# Controller.net
KiCad netlist of a schematic drawn in Altium Designer
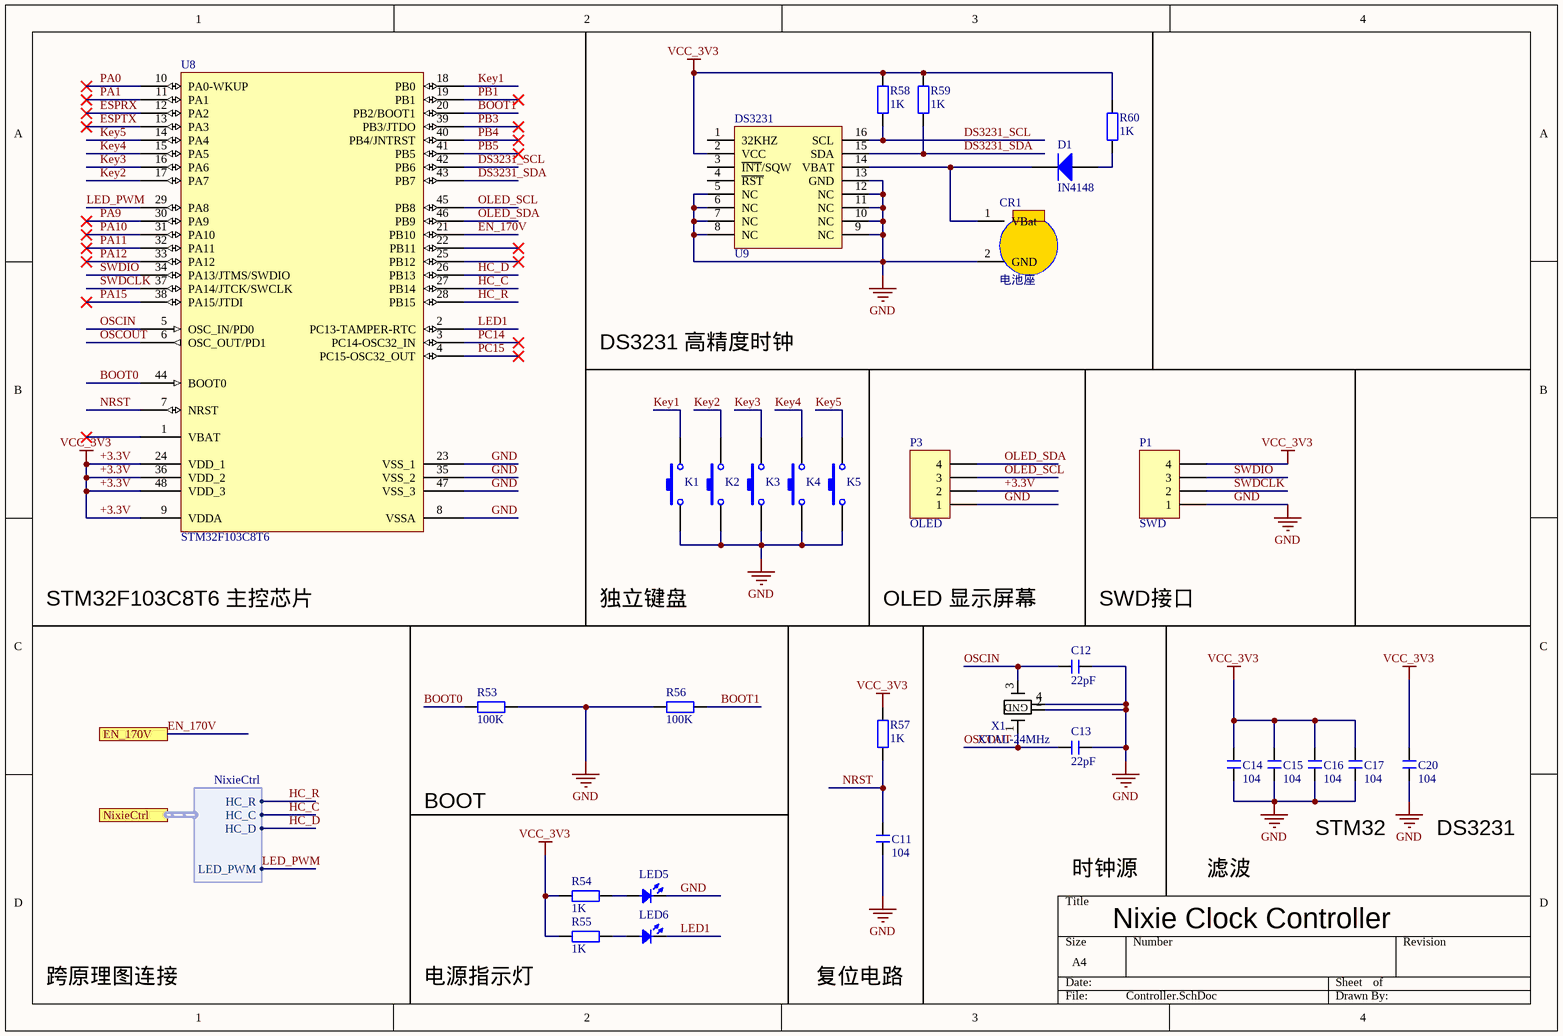
[diagram p0: Controller.SchDoc]

(export (version "E")
  (design (tool "Eeschema 10.0.6"))
  (components
    (comp (ref "C11")
      (value "104")
      (footprint "C 0603")
      (description "无极性贴片电容")
      (fields (field (name "版权归属") "源创客"))
      (libsource (lib "电阻-电容-电感") (part "C"))
    )
    (comp (ref "C12")
      (value "22pF")
      (footprint "C 0603")
      (description "无极性贴片电容")
      (fields (field (name "版权归属") "源创客"))
      (libsource (lib "电阻-电容-电感") (part "C"))
    )
    (comp (ref "C13")
      (value "22pF")
      (footprint "C 0603")
      (description "无极性贴片电容")
      (fields (field (name "版权归属") "源创客"))
      (libsource (lib "电阻-电容-电感") (part "C"))
    )
    (comp (ref "C14")
      (value "104")
      (footprint "C 0603")
      (description "无极性贴片电容")
      (fields (field (name "版权归属") "源创客"))
      (libsource (lib "电阻-电容-电感") (part "C"))
    )
    (comp (ref "C15")
      (value "104")
      (footprint "C 0603")
      (description "无极性贴片电容")
      (fields (field (name "版权归属") "源创客"))
      (libsource (lib "电阻-电容-电感") (part "C"))
    )
    (comp (ref "C16")
      (value "104")
      (footprint "C 0603")
      (description "无极性贴片电容")
      (fields (field (name "版权归属") "源创客"))
      (libsource (lib "电阻-电容-电感") (part "C"))
    )
    (comp (ref "C17")
      (value "104")
      (footprint "C 0603")
      (description "无极性贴片电容")
      (fields (field (name "版权归属") "源创客"))
      (libsource (lib "电阻-电容-电感") (part "C"))
    )
    (comp (ref "C20")
      (value "104")
      (footprint "C 0603")
      (description "无极性贴片电容")
      (fields (field (name "版权归属") "源创客"))
      (libsource (lib "电阻-电容-电感") (part "C"))
    )
    (comp (ref "CR1") (value "电池座") (footprint "BAT-2P") (libsource (lib "常用元件库") (part "CR2032 电池座")))
    (comp (ref "D1") (value "IN4148") (footprint "0805D") (libsource (lib "常用元件库") (part "二级管")))
    (comp (ref "K1") (value "按键") (footprint "TSW 3*6*4.3-S-W") (libsource (lib "常用元件库") (part "按键")))
    (comp (ref "K2") (value "按键") (footprint "TSW 3*6*4.3-S-W") (libsource (lib "常用元件库") (part "按键")))
    (comp (ref "K3") (value "按键") (footprint "TSW 3*6*4.3-S-W") (libsource (lib "常用元件库") (part "按键")))
    (comp (ref "K4") (value "按键") (footprint "TSW 3*6*4.3-S-W") (libsource (lib "常用元件库") (part "按键")))
    (comp (ref "K5") (value "按键") (footprint "TSW 3*6*4.3-S-W") (libsource (lib "常用元件库") (part "按键")))
    (comp (ref "LED5")
      (value "LED")
      (footprint "0805D")
      (fields (field (name "PUBLISHER") "Altium Limited"))
      (libsource (lib "常用元件库") (part "LED"))
    )
    (comp (ref "LED6")
      (value "LED")
      (footprint "0805D")
      (fields (field (name "PUBLISHER") "Altium Limited"))
      (libsource (lib "常用元件库") (part "LED"))
    )
    (comp (ref "P1")
      (value "SWD")
      (footprint "HDR1X4")
      (description "Header, 4-Pin")
      (fields (field (name "PUBLISHER") "Altium Limited"))
      (libsource (lib "Miscellaneous Connectors") (part "Header 4"))
    )
    (comp (ref "P3")
      (value "OLED")
      (footprint "HDR1X4")
      (description "Header, 4-Pin")
      (fields (field (name "PUBLISHER") "Altium Limited"))
      (libsource (lib "Miscellaneous Connectors") (part "Header 4"))
    )
    (comp (ref "R53")
      (value "100K")
      (footprint "R 0603")
      (description "贴片电阻")
      (fields (field (name "版权归属") "源创客"))
      (libsource (lib "电阻-电容-电感") (part "R"))
    )
    (comp (ref "R54")
      (value "1K")
      (footprint "R 0603")
      (description "贴片电阻")
      (fields (field (name "版权归属") "源创客"))
      (libsource (lib "电阻-电容-电感") (part "R"))
    )
    (comp (ref "R55")
      (value "1K")
      (footprint "R 0603")
      (description "贴片电阻")
      (fields (field (name "版权归属") "源创客"))
      (libsource (lib "电阻-电容-电感") (part "R"))
    )
    (comp (ref "R56")
      (value "100K")
      (footprint "R 0603")
      (description "贴片电阻")
      (fields (field (name "版权归属") "源创客"))
      (libsource (lib "电阻-电容-电感") (part "R"))
    )
    (comp (ref "R57")
      (value "1K")
      (footprint "R 0603")
      (description "贴片电阻")
      (fields (field (name "版权归属") "源创客"))
      (libsource (lib "电阻-电容-电感") (part "R"))
    )
    (comp (ref "R58")
      (value "1K")
      (footprint "R 0603")
      (description "贴片电阻")
      (fields (field (name "版权归属") "源创客"))
      (libsource (lib "电阻-电容-电感") (part "R"))
    )
    (comp (ref "R59")
      (value "1K")
      (footprint "R 0603")
      (description "贴片电阻")
      (fields (field (name "版权归属") "源创客"))
      (libsource (lib "电阻-电容-电感") (part "R"))
    )
    (comp (ref "R60")
      (value "1K")
      (footprint "R 0603")
      (description "贴片电阻")
      (fields (field (name "版权归属") "源创客"))
      (libsource (lib "电阻-电容-电感") (part "R"))
    )
    (comp (ref "U8")
      (value "STM32F103C8T6")
      (footprint "LQFP48 7X7_M")
      (description "Flaah:64/RAM:20/IO:36")
      (fields (field (name "版权归属") "源创客"))
      (libsource (lib "STM32系列单片机") (part "STM32F103C8T6"))
    )
    (comp (ref "U9") (value "DS3231") (footprint "SOL-16") (libsource (lib "常用元件库") (part "DS3231")))
    (comp (ref "X1")
      (value "XTAL-24MHz")
      (footprint "XTAL-3225")
      (libsource (lib "7426SCH") (part "XTAL-SMD"))
    )
  )
  (nets
    (net (code "2") (name "/BOOT0") (class "Default")
      (node (ref "R53") (pin "1") (pinfunction "1_1") (pintype "passive"))
      (node (ref "U8") (pin "44") (pinfunction "BOOT0_44") (pintype "input"))
    )
    (net (code "3") (name "/BOOT1") (class "Default")
      (node (ref "R56") (pin "2") (pinfunction "2_2") (pintype "passive"))
      (node (ref "U8") (pin "20") (pinfunction "PB2/BOOT1_20") (pintype "bidirectional"))
    )
    (net (code "4") (name "/DS3231_SCL") (class "Default")
      (node (ref "R58") (pin "1") (pinfunction "1_1") (pintype "passive"))
      (node (ref "U8") (pin "42") (pinfunction "PB6_42") (pintype "bidirectional"))
      (node (ref "U9") (pin "16") (pinfunction "SCL_16") (pintype "passive"))
    )
    (net (code "5") (name "/DS3231_SDA") (class "Default")
      (node (ref "R59") (pin "1") (pinfunction "1_1") (pintype "passive"))
      (node (ref "U8") (pin "43") (pinfunction "PB7_43") (pintype "bidirectional"))
      (node (ref "U9") (pin "15") (pinfunction "SDA_15") (pintype "passive"))
    )
    (net (code "6") (name "/EN_170V") (class "Default")
      (node (ref "U8") (pin "21") (pinfunction "PB10_21") (pintype "bidirectional"))
    )
    (net (code "7") (name "/ESPRX") (class "Default")
      (node (ref "U8") (pin "12") (pinfunction "PA2_12") (pintype "bidirectional+no_connect"))
    )
    (net (code "8") (name "/ESPTX") (class "Default")
      (node (ref "U8") (pin "13") (pinfunction "PA3_13") (pintype "bidirectional+no_connect"))
    )
    (net (code "9") (name "/HC_C") (class "Default")
      (node (ref "U8") (pin "27") (pinfunction "PB14_27") (pintype "bidirectional"))
    )
    (net (code "10") (name "/HC_D") (class "Default")
      (node (ref "U8") (pin "26") (pinfunction "PB13_26") (pintype "bidirectional"))
    )
    (net (code "11") (name "/HC_R") (class "Default")
      (node (ref "U8") (pin "28") (pinfunction "PB15_28") (pintype "bidirectional"))
    )
    (net (code "12") (name "/Key1") (class "Default")
      (node (ref "K1") (pin "2") (pinfunction "2_2") (pintype "passive"))
      (node (ref "U8") (pin "18") (pinfunction "PB0_18") (pintype "bidirectional"))
    )
    (net (code "13") (name "/Key2") (class "Default")
      (node (ref "K2") (pin "2") (pinfunction "2_2") (pintype "passive"))
      (node (ref "U8") (pin "17") (pinfunction "PA7_17") (pintype "bidirectional"))
    )
    (net (code "14") (name "/Key3") (class "Default")
      (node (ref "K3") (pin "2") (pinfunction "2_2") (pintype "passive"))
      (node (ref "U8") (pin "16") (pinfunction "PA6_16") (pintype "bidirectional"))
    )
    (net (code "15") (name "/Key4") (class "Default")
      (node (ref "K4") (pin "2") (pinfunction "2_2") (pintype "passive"))
      (node (ref "U8") (pin "15") (pinfunction "PA5_15") (pintype "bidirectional"))
    )
    (net (code "16") (name "/Key5") (class "Default")
      (node (ref "K5") (pin "2") (pinfunction "2_2") (pintype "passive"))
      (node (ref "U8") (pin "14") (pinfunction "PA4_14") (pintype "bidirectional"))
    )
    (net (code "17") (name "/LED1") (class "Default")
      (node (ref "LED6") (pin "2") (pinfunction "K_2") (pintype "passive"))
      (node (ref "U8") (pin "2") (pinfunction "PC13-TAMPER-RTC_2") (pintype "bidirectional"))
    )
    (net (code "18") (name "/LED_PWM") (class "Default")
      (node (ref "U8") (pin "29") (pinfunction "PA8_29") (pintype "bidirectional"))
    )
    (net (code "19") (name "/NRST") (class "Default")
      (node (ref "C11") (pin "2") (pinfunction "2_2") (pintype "passive"))
      (node (ref "R57") (pin "1") (pinfunction "1_1") (pintype "passive"))
      (node (ref "U8") (pin "7") (pinfunction "NRST_7") (pintype "bidirectional"))
    )
    (net (code "20") (name "/OLED_SCL") (class "Default")
      (node (ref "P3") (pin "3") (pinfunction "3_3") (pintype "passive"))
      (node (ref "U8") (pin "45") (pinfunction "PB8_45") (pintype "bidirectional"))
    )
    (net (code "21") (name "/OLED_SDA") (class "Default")
      (node (ref "P3") (pin "4") (pinfunction "4_4") (pintype "passive"))
      (node (ref "U8") (pin "46") (pinfunction "PB9_46") (pintype "bidirectional"))
    )
    (net (code "22") (name "/OSCIN") (class "Default")
      (node (ref "C12") (pin "1") (pinfunction "1_1") (pintype "passive"))
      (node (ref "U8") (pin "5") (pinfunction "OSC_IN/PD0_5") (pintype "input"))
      (node (ref "X1") (pin "3") (pinfunction "GND_3") (pintype "power_in"))
    )
    (net (code "23") (name "/OSCOUT") (class "Default")
      (node (ref "C13") (pin "1") (pinfunction "1_1") (pintype "passive"))
      (node (ref "U8") (pin "6") (pinfunction "OSC_OUT/PD1_6") (pintype "output"))
      (node (ref "X1") (pin "1") (pintype "bidirectional"))
    )
    (net (code "24") (name "/PA0") (class "Default")
      (node (ref "U8") (pin "10") (pinfunction "PA0-WKUP_10") (pintype "bidirectional+no_connect"))
    )
    (net (code "25") (name "/PA1") (class "Default")
      (node (ref "U8") (pin "11") (pinfunction "PA1_11") (pintype "bidirectional+no_connect"))
    )
    (net (code "26") (name "/PA9") (class "Default")
      (node (ref "U8") (pin "30") (pinfunction "PA9_30") (pintype "bidirectional+no_connect"))
    )
    (net (code "27") (name "/PA10") (class "Default")
      (node (ref "U8") (pin "31") (pinfunction "PA10_31") (pintype "bidirectional+no_connect"))
    )
    (net (code "28") (name "/PA11") (class "Default")
      (node (ref "U8") (pin "32") (pinfunction "PA11_32") (pintype "bidirectional+no_connect"))
    )
    (net (code "29") (name "/PA12") (class "Default")
      (node (ref "U8") (pin "33") (pinfunction "PA12_33") (pintype "bidirectional+no_connect"))
    )
    (net (code "30") (name "/PA15") (class "Default")
      (node (ref "U8") (pin "38") (pinfunction "PA15/JTDI_38") (pintype "bidirectional+no_connect"))
    )
    (net (code "31") (name "/PB1") (class "Default")
      (node (ref "U8") (pin "19") (pinfunction "PB1_19") (pintype "bidirectional+no_connect"))
    )
    (net (code "32") (name "/PB3") (class "Default")
      (node (ref "U8") (pin "39") (pinfunction "PB3/JTDO_39") (pintype "bidirectional+no_connect"))
    )
    (net (code "33") (name "/PB4") (class "Default")
      (node (ref "U8") (pin "40") (pinfunction "PB4/JNTRST_40") (pintype "bidirectional+no_connect"))
    )
    (net (code "34") (name "/PB5") (class "Default")
      (node (ref "U8") (pin "41") (pinfunction "PB5_41") (pintype "bidirectional+no_connect"))
    )
    (net (code "35") (name "/PC14") (class "Default")
      (node (ref "U8") (pin "3") (pinfunction "PC14-OSC32_IN_3") (pintype "bidirectional+no_connect"))
    )
    (net (code "36") (name "/PC15") (class "Default")
      (node (ref "U8") (pin "4") (pinfunction "PC15-OSC32_OUT_4") (pintype "bidirectional+no_connect"))
    )
    (net (code "37") (name "/SWDCLK") (class "Default")
      (node (ref "P1") (pin "2") (pinfunction "2_2") (pintype "passive"))
      (node (ref "U8") (pin "37") (pinfunction "PA14/JTCK/SWCLK_37") (pintype "bidirectional"))
    )
    (net (code "38") (name "/SWDIO") (class "Default")
      (node (ref "P1") (pin "3") (pinfunction "3_3") (pintype "passive"))
      (node (ref "U8") (pin "34") (pinfunction "PA13/JTMS/SWDIO_34") (pintype "bidirectional"))
    )
    (net (code "40") (name "GND") (class "Default")
      (node (ref "C11") (pin "1") (pinfunction "1_1") (pintype "passive"))
      (node (ref "C12") (pin "2") (pinfunction "2_2") (pintype "passive"))
      (node (ref "C13") (pin "2") (pinfunction "2_2") (pintype "passive"))
      (node (ref "C14") (pin "2") (pinfunction "2_2") (pintype "passive"))
      (node (ref "C15") (pin "2") (pinfunction "2_2") (pintype "passive"))
      (node (ref "C16") (pin "2") (pinfunction "2_2") (pintype "passive"))
      (node (ref "C17") (pin "2") (pinfunction "2_2") (pintype "passive"))
      (node (ref "C20") (pin "1") (pinfunction "1_1") (pintype "passive"))
      (node (ref "CR1") (pin "2") (pinfunction "GND_2") (pintype "power_in"))
      (node (ref "K1") (pin "1") (pinfunction "1_1") (pintype "passive"))
      (node (ref "K2") (pin "1") (pinfunction "1_1") (pintype "passive"))
      (node (ref "K3") (pin "1") (pinfunction "1_1") (pintype "passive"))
      (node (ref "K4") (pin "1") (pinfunction "1_1") (pintype "passive"))
      (node (ref "K5") (pin "1") (pinfunction "1_1") (pintype "passive"))
      (node (ref "LED5") (pin "2") (pinfunction "K_2") (pintype "passive"))
      (node (ref "P1") (pin "1") (pinfunction "1_1") (pintype "passive"))
      (node (ref "P3") (pin "1") (pinfunction "1_1") (pintype "passive"))
      (node (ref "R53") (pin "2") (pinfunction "2_2") (pintype "passive"))
      (node (ref "R56") (pin "1") (pinfunction "1_1") (pintype "passive"))
      (node (ref "U8") (pin "23") (pinfunction "VSS_1_23") (pintype "power_in"))
      (node (ref "U8") (pin "35") (pinfunction "VSS_2_35") (pintype "power_in"))
      (node (ref "U8") (pin "47") (pinfunction "VSS_3_47") (pintype "power_in"))
      (node (ref "U8") (pin "8") (pinfunction "VSSA_8") (pintype "power_in"))
      (node (ref "U9") (pin "10") (pinfunction "NC_10") (pintype "passive"))
      (node (ref "U9") (pin "11") (pinfunction "NC_11") (pintype "passive"))
      (node (ref "U9") (pin "12") (pinfunction "NC_12") (pintype "passive"))
      (node (ref "U9") (pin "13") (pinfunction "GND_13") (pintype "passive"))
      (node (ref "U9") (pin "5") (pinfunction "NC_5") (pintype "passive"))
      (node (ref "U9") (pin "6") (pinfunction "NC_6") (pintype "passive"))
      (node (ref "U9") (pin "7") (pinfunction "NC_7") (pintype "passive"))
      (node (ref "U9") (pin "8") (pinfunction "NC_8") (pintype "passive"))
      (node (ref "U9") (pin "9") (pinfunction "NC_9") (pintype "passive"))
      (node (ref "X1") (pin "2") (pintype "power_in"))
      (node (ref "X1") (pin "4") (pintype "passive"))
    )
    (net (code "41") (name "Net-(CR1-VBat)") (class "Default")
      (node (ref "CR1") (pin "1") (pinfunction "VBat_1") (pintype "power_in"))
      (node (ref "D1") (pin "2") (pinfunction "K_2") (pintype "passive"))
      (node (ref "U9") (pin "14") (pinfunction "VBAT_14") (pintype "passive"))
    )
    (net (code "42") (name "Net-(D1-A)") (class "Default")
      (node (ref "D1") (pin "1") (pinfunction "A_1") (pintype "passive"))
      (node (ref "R60") (pin "2") (pinfunction "2_2") (pintype "passive"))
    )
    (net (code "43") (name "Net-(LED5-A)") (class "Default")
      (node (ref "LED5") (pin "1") (pinfunction "A_1") (pintype "passive"))
      (node (ref "R54") (pin "2") (pinfunction "2_2") (pintype "passive"))
    )
    (net (code "44") (name "Net-(LED6-A)") (class "Default")
      (node (ref "LED6") (pin "1") (pinfunction "A_1") (pintype "passive"))
      (node (ref "R55") (pin "2") (pinfunction "2_2") (pintype "passive"))
    )
    (net (code "45") (name "VCC_3V3") (class "Default")
      (node (ref "C14") (pin "1") (pinfunction "1_1") (pintype "passive"))
      (node (ref "C15") (pin "1") (pinfunction "1_1") (pintype "passive"))
      (node (ref "C16") (pin "1") (pinfunction "1_1") (pintype "passive"))
      (node (ref "C17") (pin "1") (pinfunction "1_1") (pintype "passive"))
      (node (ref "C20") (pin "2") (pinfunction "2_2") (pintype "passive"))
      (node (ref "P1") (pin "4") (pinfunction "4_4") (pintype "passive"))
      (node (ref "P3") (pin "2") (pinfunction "2_2") (pintype "passive"))
      (node (ref "R54") (pin "1") (pinfunction "1_1") (pintype "passive"))
      (node (ref "R55") (pin "1") (pinfunction "1_1") (pintype "passive"))
      (node (ref "R57") (pin "2") (pinfunction "2_2") (pintype "passive"))
      (node (ref "R58") (pin "2") (pinfunction "2_2") (pintype "passive"))
      (node (ref "R59") (pin "2") (pinfunction "2_2") (pintype "passive"))
      (node (ref "R60") (pin "1") (pinfunction "1_1") (pintype "passive"))
      (node (ref "U8") (pin "24") (pinfunction "VDD_1_24") (pintype "power_in"))
      (node (ref "U8") (pin "36") (pinfunction "VDD_2_36") (pintype "power_in"))
      (node (ref "U8") (pin "48") (pinfunction "VDD_3_48") (pintype "power_in"))
      (node (ref "U8") (pin "9") (pinfunction "VDDA_9") (pintype "power_in"))
      (node (ref "U9") (pin "2") (pinfunction "VCC_2") (pintype "passive"))
    )
    (net (code "46") (name "unconnected-(U8-PB11-Pad22)") (class "Default")
      (node (ref "U8") (pin "22") (pinfunction "PB11_22") (pintype "bidirectional+no_connect"))
    )
    (net (code "47") (name "unconnected-(U8-PB12-Pad25)") (class "Default")
      (node (ref "U8") (pin "25") (pinfunction "PB12_25") (pintype "bidirectional+no_connect"))
    )
    (net (code "48") (name "unconnected-(U8-VBAT-Pad1)") (class "Default")
      (node (ref "U8") (pin "1") (pinfunction "VBAT_1") (pintype "power_in+no_connect"))
    )
    (net (code "49") (name "unconnected-(U9-32KHZ-Pad1)") (class "Default")
      (node (ref "U9") (pin "1") (pinfunction "32KHZ_1") (pintype "passive"))
    )
    (net (code "50") (name "unconnected-(U9-~{INT}{slash}SQW-Pad3)") (class "Default")
      (node (ref "U9") (pin "3") (pinfunction "~{INT}/SQW_3") (pintype "passive"))
    )
    (net (code "51") (name "unconnected-(U9-~{RST}-Pad4)") (class "Default")
      (node (ref "U9") (pin "4") (pinfunction "~{RST}_4") (pintype "passive"))
    )
  )
)
